# LMZM33603.net
KiCad netlist of a schematic drawn in Altium Designer
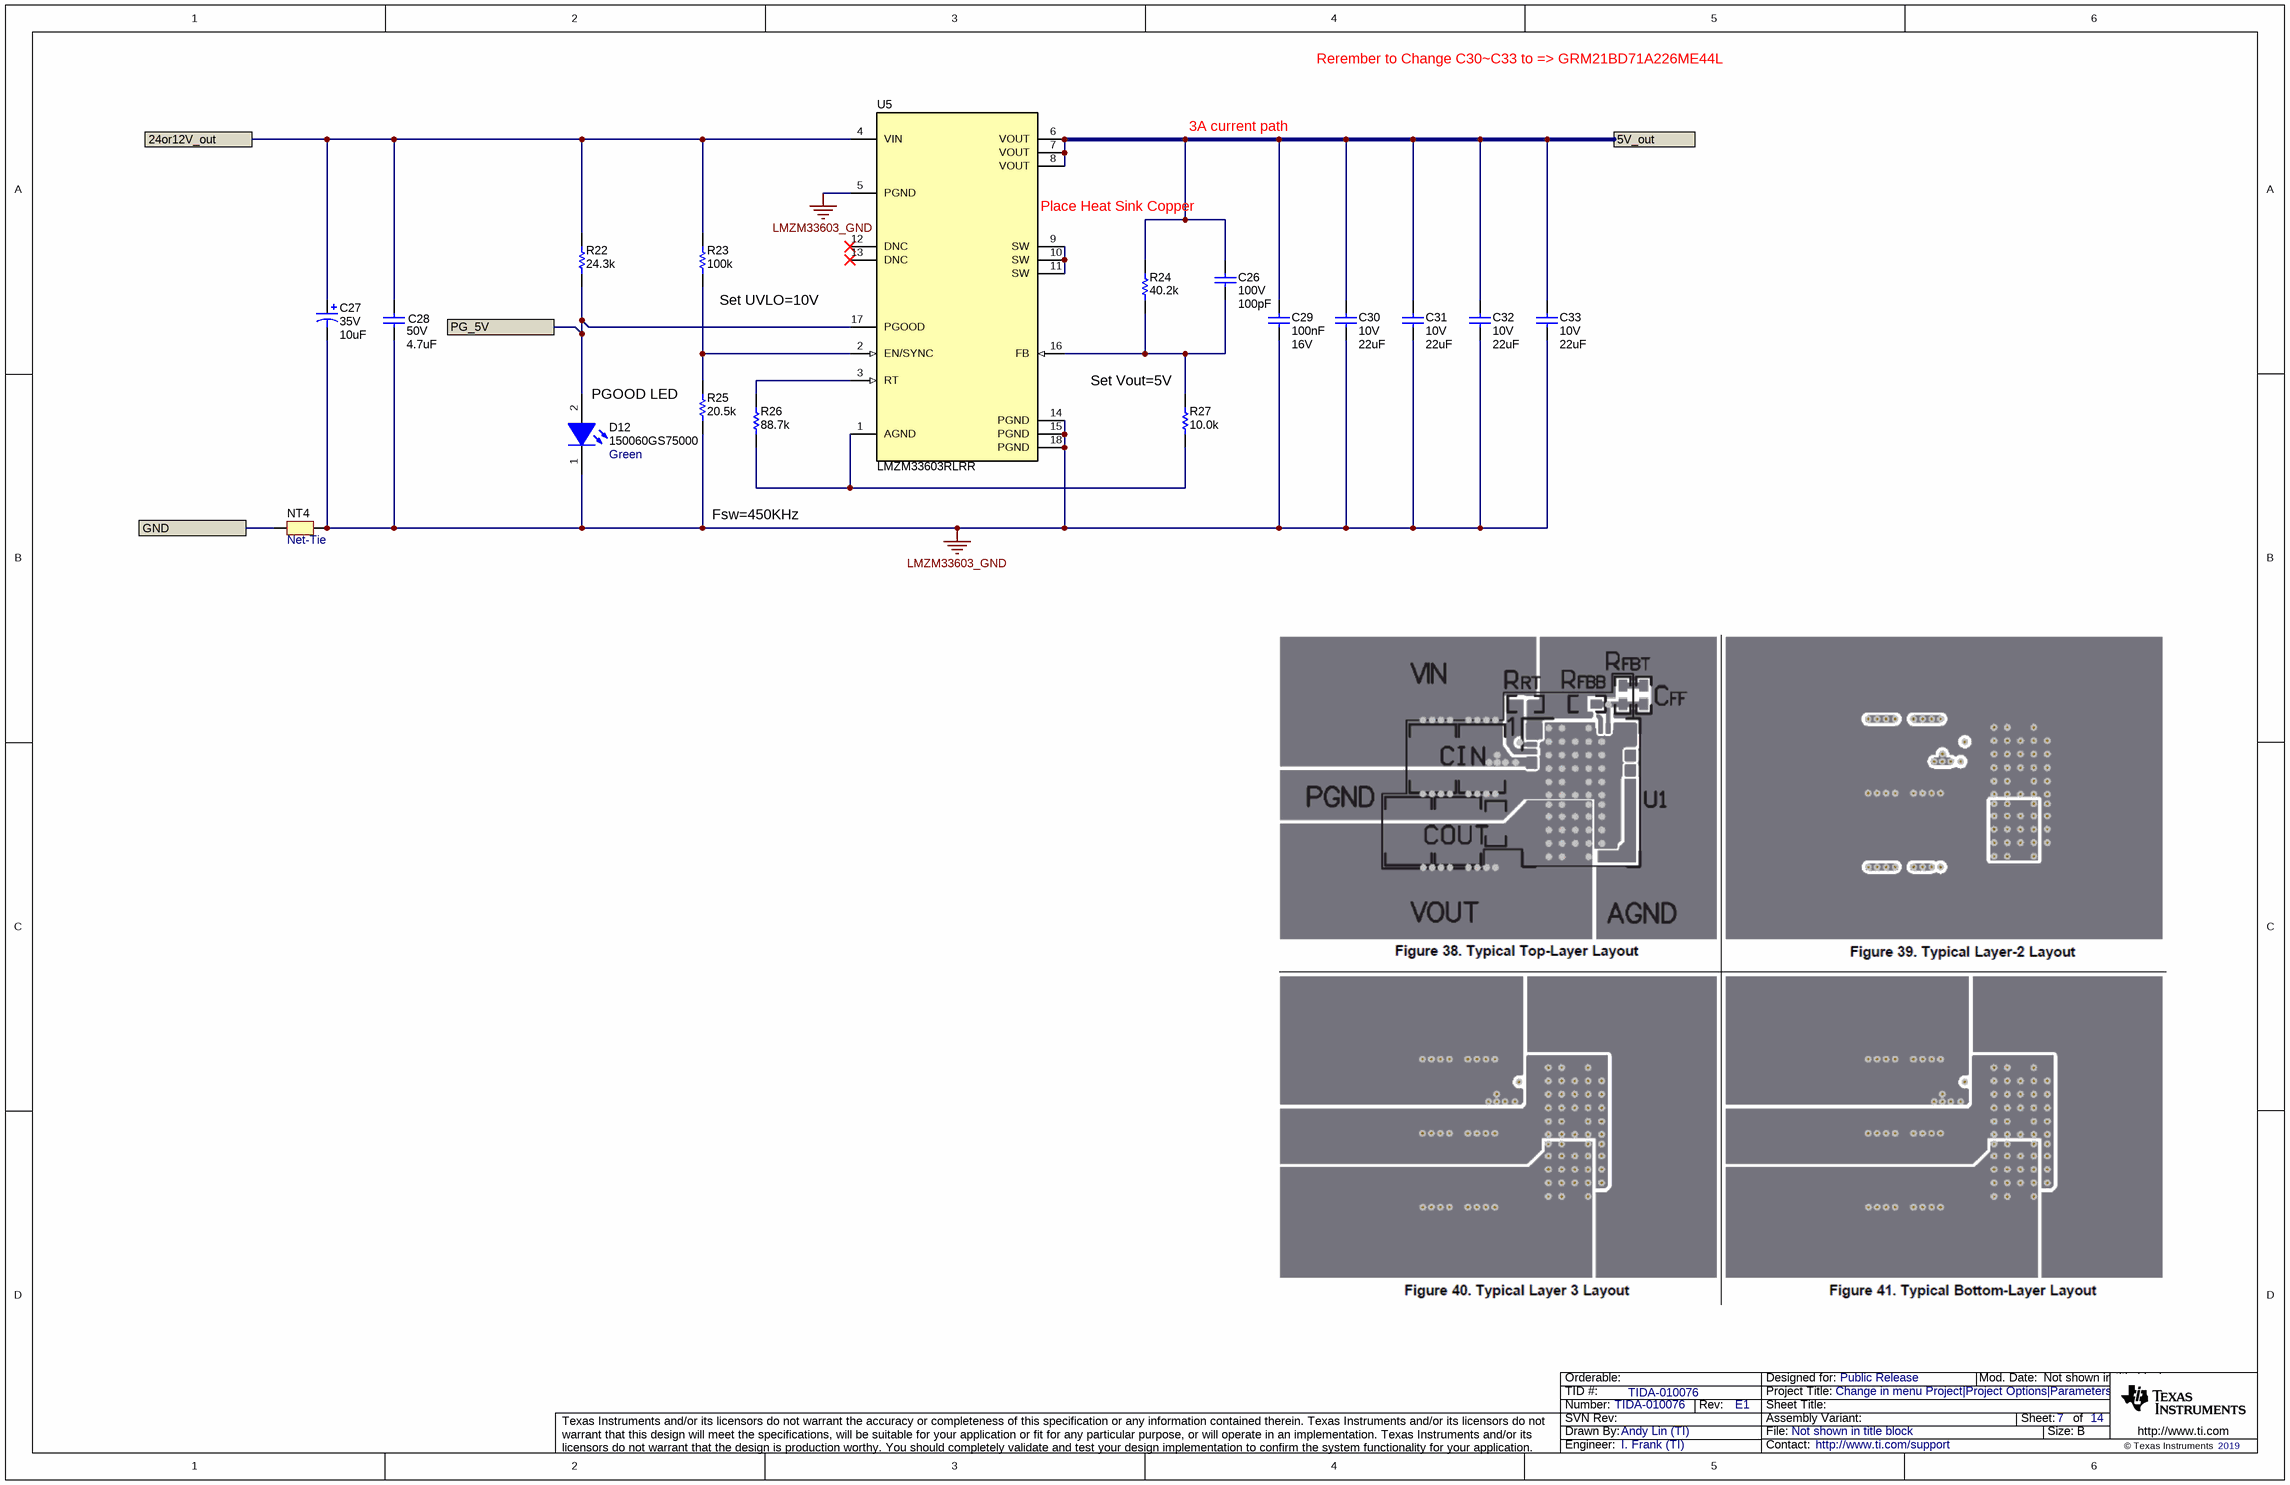
[diagram p0: LMZM33603.SchDoc]

(export (version "E")
  (design (tool "Eeschema 10.0.6"))
  (components
    (comp (ref "C26")
      (value "GRM1885C2A101JA01D")
      (footprint "0603")
      (description "CAP, CERM, 100 pF, 100 V, +/- 5%, C0G/NP0, 0603")
      (fields
        (field (name "MANUFACTURER") "MuRata")
        (field (name "VDC_V") "100V")
        (field (name "VALUEDISPLAYED") "100pF")
        (field (name "PUBLISHER") "Texas Instruments")
      )
      (libsource (lib "Altium Vault - TI") (part "Capacitor"))
    )
    (comp (ref "C27")
      (value "593D106X9035D2TE3")
      (footprint "7343-31")
      (description "CAP, TA, 10 uF, 35 V, +/- 10%, 0.3 ohm, SMD")
      (fields
        (field (name "MANUFACTURER") "Vishay-Sprague")
        (field (name "VDC_V") "35V")
        (field (name "VALUEDISPLAYED") "10uF")
        (field (name "PUBLISHER") "Texas Instruments")
      )
      (libsource (lib "Altium Vault - TI") (part "Cap_Polarized"))
    )
    (comp (ref "C28")
      (value "GRM32ER71H475KA88L")
      (footprint "1210_270")
      (description "CAP, CERM, 4.7 uF, 50 V, +/- 10%, X7R, 1210")
      (fields
        (field (name "MANUFACTURER") "MuRata")
        (field (name "VDC_V") "50V")
        (field (name "VALUEDISPLAYED") "4.7uF")
        (field (name "PUBLISHER") "Texas Instruments")
      )
      (libsource (lib "Altium Vault - TI") (part "Capacitor"))
    )
    (comp (ref "C29")
      (value "GRM188R71C104KA01D")
      (footprint "0603")
      (description "CAP, CERM, 0.1 uF, 16 V, +/- 10%, X7R, 0603")
      (fields
        (field (name "MANUFACTURER") "MuRata")
        (field (name "CAP_F") "100nF")
        (field (name "VDC_V") "16V")
        (field (name "PUBLISHER") "Texas Instruments")
      )
      (libsource (lib "Altium Vault - TI") (part "Capacitor"))
    )
    (comp (ref "C30")
      (value "GRM21BZ71A226ME15L")
      (footprint "0805_HV")
      (description "CAP, CERM, 22 uF, 10 V, +/- 20%, X7R, 0805")
      (fields
        (field (name "VDC_V") "10V")
        (field (name "VALUEDISPLAYED") "22uF")
        (field (name "MANUFACTURER") "MuRata")
        (field (name "PUBLISHER") "Texas Instruments")
      )
      (libsource (lib "Altium Vault - TI") (part "Capacitor"))
    )
    (comp (ref "C31")
      (value "GRM21BZ71A226ME15L")
      (footprint "0805_HV")
      (description "CAP, CERM, 22 uF, 10 V, +/- 20%, X7R, 0805")
      (fields
        (field (name "VDC_V") "10V")
        (field (name "VALUEDISPLAYED") "22uF")
        (field (name "MANUFACTURER") "MuRata")
        (field (name "PUBLISHER") "Texas Instruments")
      )
      (libsource (lib "Altium Vault - TI") (part "Capacitor"))
    )
    (comp (ref "C32")
      (value "GRM21BZ71A226ME15L")
      (footprint "0805_HV")
      (description "CAP, CERM, 22 uF, 10 V, +/- 20%, X7R, 0805")
      (fields
        (field (name "VDC_V") "10V")
        (field (name "VALUEDISPLAYED") "22uF")
        (field (name "MANUFACTURER") "MuRata")
        (field (name "PUBLISHER") "Texas Instruments")
      )
      (libsource (lib "Altium Vault - TI") (part "Capacitor"))
    )
    (comp (ref "C33")
      (value "GRM21BZ71A226ME15L")
      (footprint "0805_HV")
      (description "CAP, CERM, 22 uF, 10 V, +/- 20%, X7R, 0805")
      (fields
        (field (name "VDC_V") "10V")
        (field (name "VALUEDISPLAYED") "22uF")
        (field (name "MANUFACTURER") "MuRata")
        (field (name "PUBLISHER") "Texas Instruments")
      )
      (libsource (lib "Altium Vault - TI") (part "Capacitor"))
    )
    (comp (ref "D12")
      (value "150060GS75000")
      (footprint "WL-SMCW_GREEN")
      (description "LED, Green, SMD")
      (fields (field (name "ALTIUM_VALUE") "Green") (field (name "MANUFACTURER") "Wurth Elektronik"))
      (libsource (lib "Altium Vault - TI") (part "LED_A2_K1"))
    )
    (comp (ref "NT4")
      (value "Net-Tie")
      (footprint "Net-Tie_50milWide_30milLong")
      (description "Single point connection between nets.")
      (libsource (lib "Altium Vault - TI") (part "Net-Tie"))
    )
    (comp (ref "R22")
      (value "CRCW060324K3FKEA")
      (footprint "0603")
      (description "RES, 24.3 k, 1%, 0.1 W, 0603")
      (fields
        (field (name "MANUFACTURER") "Vishay-Dale")
        (field (name "VALUEDISPLAYED") "24.3k")
        (field (name "PUBLISHER") "Texas Instruments")
      )
      (libsource (lib "Altium Vault - TI") (part "Resistor"))
    )
    (comp (ref "R23")
      (value "CRCW0402100KFKED")
      (footprint "0402")
      (description "RES, 100 k, 1%, 0.063 W, AEC-Q200 Grade 0, 0402")
      (fields (field (name "MANUFACTURER") "Vishay-Dale") (field (name "VALUEDISPLAYED") "100k"))
      (libsource (lib "Altium Vault - TI") (part "Resistor"))
    )
    (comp (ref "R24")
      (value "CRCW040240K2FKED")
      (footprint "0402")
      (description "RES, 40.2 k, 1%, 0.063 W, AEC-Q200 Grade 0, 0402")
      (fields (field (name "MANUFACTURER") "Vishay-Dale") (field (name "VALUEDISPLAYED") "40.2k"))
      (libsource (lib "Altium Vault - TI") (part "Resistor"))
    )
    (comp (ref "R25")
      (value "CRCW040220K5FKED")
      (footprint "0402")
      (description "RES, 20.5 k, 1%, 0.063 W, AEC-Q200 Grade 0, 0402")
      (fields (field (name "MANUFACTURER") "Vishay-Dale") (field (name "VALUEDISPLAYED") "20.5k"))
      (libsource (lib "Altium Vault - TI") (part "Resistor"))
    )
    (comp (ref "R26")
      (value "CRCW040288K7FKED")
      (footprint "0402")
      (description "RES, 88.7 k, 1%, 0.063 W, AEC-Q200 Grade 0, 0402")
      (fields (field (name "MANUFACTURER") "Vishay-Dale") (field (name "VALUEDISPLAYED") "88.7k"))
      (libsource (lib "Altium Vault - TI") (part "Resistor"))
    )
    (comp (ref "R27")
      (value "CRCW040210K0FKED")
      (footprint "0402")
      (description "RES, 10.0 k, 1%, 0.063 W, AEC-Q200 Grade 0, 0402")
      (fields (field (name "MANUFACTURER") "Vishay-Dale") (field (name "VALUEDISPLAYED") "10.0k"))
      (libsource (lib "Altium Vault - TI") (part "Resistor"))
    )
    (comp (ref "U5")
      (value "LMZM33603RLRR")
      (footprint "RLR0018A")
      (description "4V to 36V, 2A Step-Down DC/DC Power Module in Compact 7x9x4mm QFN Package, RLR0018A (B3QFN-18)")
      (fields
        (field (name "ALTERNATE PARTNUMBER") "LMZM33603RLRT")
        (field (name "MANUFACTURER") "Texas Instruments")
        (field (name "PARTNUMBER") "LMZM33603RLRR")
      )
      (libsource (lib "Altium Vault - TI") (part "LMZM3360x"))
    )
  )
  (nets
    (net (code "1") (name "/5V_out") (class "Default")
      (node (ref "C26") (pin "1") (pinfunction "1_1") (pintype "passive"))
      (node (ref "C29") (pin "1") (pinfunction "1_1") (pintype "passive"))
      (node (ref "C30") (pin "1") (pinfunction "1_1") (pintype "passive"))
      (node (ref "C31") (pin "1") (pinfunction "1_1") (pintype "passive"))
      (node (ref "C32") (pin "1") (pinfunction "1_1") (pintype "passive"))
      (node (ref "C33") (pin "1") (pinfunction "1_1") (pintype "passive"))
      (node (ref "R24") (pin "2") (pinfunction "2_2") (pintype "passive"))
      (node (ref "U5") (pin "6") (pinfunction "VOUT_6") (pintype "power_in"))
      (node (ref "U5") (pin "7") (pinfunction "VOUT_7") (pintype "power_in"))
      (node (ref "U5") (pin "8") (pinfunction "VOUT_8") (pintype "power_in"))
    )
    (net (code "2") (name "/24or12V_out") (class "Default")
      (node (ref "C27") (pin "1") (pinfunction "+_1") (pintype "passive"))
      (node (ref "C28") (pin "1") (pinfunction "1_1") (pintype "passive"))
      (node (ref "R22") (pin "2") (pinfunction "2_2") (pintype "passive"))
      (node (ref "R23") (pin "2") (pinfunction "2_2") (pintype "passive"))
      (node (ref "U5") (pin "4") (pinfunction "VIN_4") (pintype "power_in"))
    )
    (net (code "3") (name "/GND") (class "Default")
      (node (ref "NT4") (pin "1") (pinfunction "1_1") (pintype "passive"))
    )
    (net (code "4") (name "/PG_5V") (class "Default")
      (node (ref "D12") (pin "2") (pinfunction "A_2") (pintype "passive"))
      (node (ref "R22") (pin "1") (pinfunction "1_1") (pintype "passive"))
      (node (ref "U5") (pin "17") (pinfunction "PGOOD_17") (pintype "passive"))
    )
    (net (code "5") (name "LMZM33603_GND") (class "Default")
      (node (ref "C27") (pin "2") (pinfunction "-_2") (pintype "passive"))
      (node (ref "C28") (pin "2") (pinfunction "2_2") (pintype "passive"))
      (node (ref "C29") (pin "2") (pinfunction "2_2") (pintype "passive"))
      (node (ref "C30") (pin "2") (pinfunction "2_2") (pintype "passive"))
      (node (ref "C31") (pin "2") (pinfunction "2_2") (pintype "passive"))
      (node (ref "C32") (pin "2") (pinfunction "2_2") (pintype "passive"))
      (node (ref "C33") (pin "2") (pinfunction "2_2") (pintype "passive"))
      (node (ref "D12") (pin "1") (pinfunction "K_1") (pintype "passive"))
      (node (ref "NT4") (pin "2") (pinfunction "2_2") (pintype "passive"))
      (node (ref "R25") (pin "1") (pinfunction "1_1") (pintype "passive"))
      (node (ref "U5") (pin "14") (pinfunction "PGND_14") (pintype "power_in"))
      (node (ref "U5") (pin "15") (pinfunction "PGND_15") (pintype "power_in"))
      (node (ref "U5") (pin "18") (pinfunction "PGND_18") (pintype "power_in"))
      (node (ref "U5") (pin "5") (pinfunction "PGND_5") (pintype "power_in"))
    )
    (net (code "6") (name "Net-(U5-AGND)") (class "Default")
      (node (ref "R26") (pin "1") (pinfunction "1_1") (pintype "passive"))
      (node (ref "R27") (pin "1") (pinfunction "1_1") (pintype "passive"))
      (node (ref "U5") (pin "1") (pinfunction "AGND_1") (pintype "power_in"))
    )
    (net (code "7") (name "Net-(U5-EN{slash}SYNC)") (class "Default")
      (node (ref "R23") (pin "1") (pinfunction "1_1") (pintype "passive"))
      (node (ref "R25") (pin "2") (pinfunction "2_2") (pintype "passive"))
      (node (ref "U5") (pin "2") (pinfunction "EN/SYNC_2") (pintype "input"))
    )
    (net (code "8") (name "Net-(U5-FB)") (class "Default")
      (node (ref "C26") (pin "2") (pinfunction "2_2") (pintype "passive"))
      (node (ref "R24") (pin "1") (pinfunction "1_1") (pintype "passive"))
      (node (ref "R27") (pin "2") (pinfunction "2_2") (pintype "passive"))
      (node (ref "U5") (pin "16") (pinfunction "FB_16") (pintype "input"))
    )
    (net (code "9") (name "Net-(U5-RT)") (class "Default")
      (node (ref "R26") (pin "2") (pinfunction "2_2") (pintype "passive"))
      (node (ref "U5") (pin "3") (pinfunction "RT_3") (pintype "input"))
    )
    (net (code "10") (name "Net-(U5-SW-Pad10)") (class "Default")
      (node (ref "U5") (pin "10") (pinfunction "SW_10") (pintype "power_in"))
      (node (ref "U5") (pin "11") (pinfunction "SW_11") (pintype "power_in"))
      (node (ref "U5") (pin "9") (pinfunction "SW_9") (pintype "power_in"))
    )
    (net (code "11") (name "unconnected-(U5-DNC-Pad12)") (class "Default")
      (node (ref "U5") (pin "12") (pinfunction "DNC_12") (pintype "passive+no_connect"))
    )
    (net (code "12") (name "unconnected-(U5-DNC-Pad13)") (class "Default")
      (node (ref "U5") (pin "13") (pinfunction "DNC_13") (pintype "passive+no_connect"))
    )
  )
)
